# Sheet1_MCU.net
KiCad netlist of a schematic drawn in Altium Designer
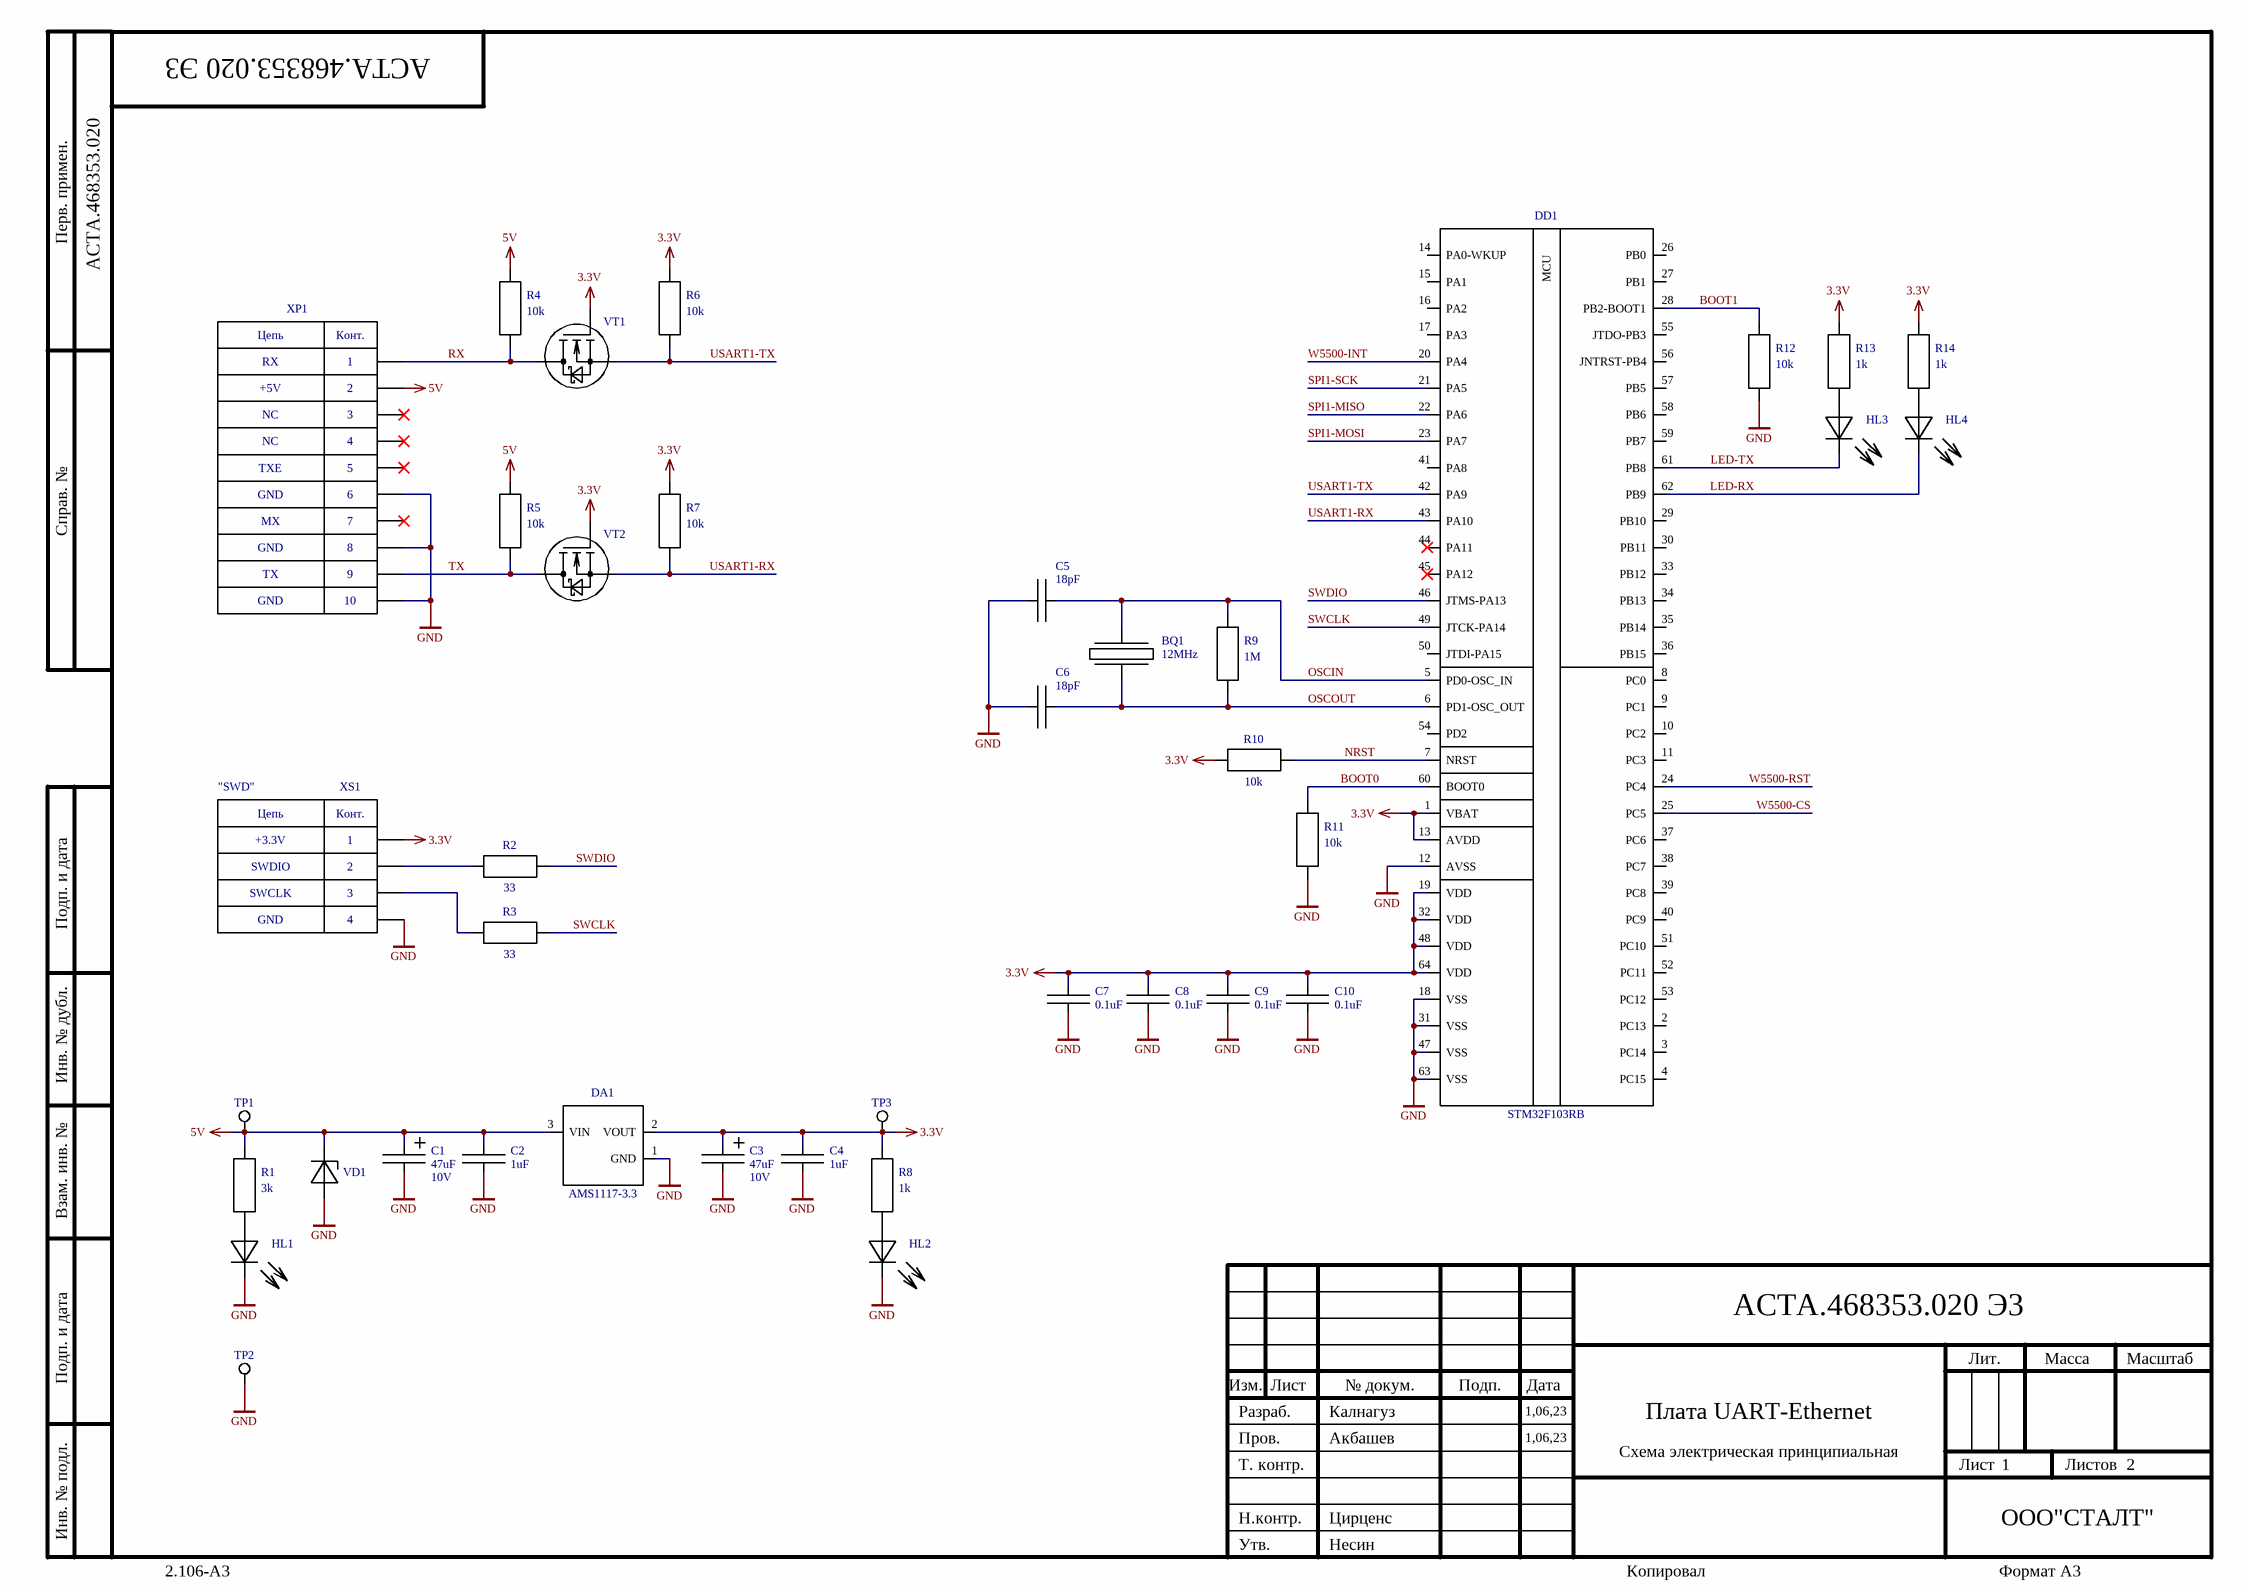
[diagram p0: Sheet1_MCU.SchDoc]

(export (version "E")
  (design (tool "Eeschema 10.0.6"))
  (components
    (comp (ref "BQ1")
      (value "12MHz")
      (footprint "HT-49S")
      (fields (field (name "Comment") "HT-49S_Rated"))
      (libsource (lib "Resonators") (part "HT-49S_Rated"))
    )
    (comp (ref "C1")
      (value "47uF")
      (footprint "CaseB_TantalumCap")
      (fields (field (name "VOLTAGE") "10V") (field (name "Comment") "CaseB_TantalumCap"))
      (libsource (lib "Tantalum_Capacitors") (part "CaseB_TantalumCap"))
    )
    (comp (ref "C2")
      (value "1uF")
      (footprint "CAP0805")
      (fields (field (name "Comment") "CAP0805_Rated"))
      (libsource (lib "Ceramic_Capacitors") (part "CAP0805_Rated"))
    )
    (comp (ref "C3")
      (value "47uF")
      (footprint "CaseB_TantalumCap")
      (fields (field (name "VOLTAGE") "10V") (field (name "Comment") "CaseB_TantalumCap"))
      (libsource (lib "Tantalum_Capacitors") (part "CaseB_TantalumCap"))
    )
    (comp (ref "C4")
      (value "1uF")
      (footprint "CAP0805")
      (fields (field (name "Comment") "CAP0805_Rated"))
      (libsource (lib "Ceramic_Capacitors") (part "CAP0805_Rated"))
    )
    (comp (ref "C5")
      (value "18pF")
      (footprint "CAP0805")
      (fields (field (name "Comment") "CAP0805_Rated"))
      (libsource (lib "Ceramic_Capacitors") (part "CAP0805_Rated"))
    )
    (comp (ref "C6")
      (value "18pF")
      (footprint "CAP0805")
      (fields (field (name "Comment") "CAP0805_Rated"))
      (libsource (lib "Ceramic_Capacitors") (part "CAP0805_Rated"))
    )
    (comp (ref "C7")
      (value "0.1uF")
      (footprint "CAP0805")
      (fields (field (name "Comment") "CAP0805_Rated"))
      (libsource (lib "Ceramic_Capacitors") (part "CAP0805_Rated"))
    )
    (comp (ref "C8")
      (value "0.1uF")
      (footprint "CAP0805")
      (fields (field (name "Comment") "CAP0805_Rated"))
      (libsource (lib "Ceramic_Capacitors") (part "CAP0805_Rated"))
    )
    (comp (ref "C9")
      (value "0.1uF")
      (footprint "CAP0805")
      (fields (field (name "Comment") "CAP0805_Rated"))
      (libsource (lib "Ceramic_Capacitors") (part "CAP0805_Rated"))
    )
    (comp (ref "C10")
      (value "0.1uF")
      (footprint "CAP0805")
      (fields (field (name "Comment") "CAP0805_Rated"))
      (libsource (lib "Ceramic_Capacitors") (part "CAP0805_Rated"))
    )
    (comp (ref "DA1")
      (value "AMS1117-3.3")
      (footprint "SOT-223")
      (description "Fixed Voltage 3.3V 1A Low Dropout Voltage Regulator")
      (libsource (lib "Power_Management_ICs") (part "AMS1117-3.3"))
    )
    (comp (ref "DD1")
      (value "STM32F103RB")
      (footprint "LQFP-64")
      (description "ARM Cortex-M3 MCU")
      (libsource (lib "MCU") (part "STM32F103RB"))
    )
    (comp (ref "HL1")
      (value "KPTD-3216MGC")
      (footprint "KPTD-3216 Green")
      (description "3.2x1.6mm SMD LED Mega Green")
      (libsource (lib "LEDs_SMD") (part "KPTD-3216MGC"))
    )
    (comp (ref "HL2")
      (value "KPTD-3216MGC")
      (footprint "KPTD-3216 Green")
      (description "3.2x1.6mm SMD LED Mega Green")
      (libsource (lib "LEDs_SMD") (part "KPTD-3216MGC"))
    )
    (comp (ref "HL3")
      (value "KPTD-3216MGC")
      (footprint "KPTD-3216 Green")
      (description "3.2x1.6mm SMD LED Mega Green")
      (libsource (lib "LEDs_SMD") (part "KPTD-3216MGC"))
    )
    (comp (ref "HL4")
      (value "KPTD-3216SYC")
      (footprint "KPTD-3216 Yellow")
      (description "3.2x1.6mm SMD LED Super Bright Yellow")
      (libsource (lib "LEDs_SMD") (part "KPTD-3216SYC"))
    )
    (comp (ref "R1")
      (value "3k")
      (footprint "RES0805")
      (fields (field (name "TOLERANCE") "5%") (field (name "Comment") "RES0805_Rated"))
      (libsource (lib "") (part "RES0805_Rated_1"))
    )
    (comp (ref "R2")
      (value "33")
      (footprint "RES0805")
      (fields (field (name "TOLERANCE") "5%") (field (name "Comment") "RES0805_Rated"))
      (libsource (lib "Resistors") (part "RES0805_Rated"))
    )
    (comp (ref "R3")
      (value "33")
      (footprint "RES0805")
      (fields (field (name "TOLERANCE") "5%") (field (name "Comment") "RES0805_Rated"))
      (libsource (lib "Resistors") (part "RES0805_Rated"))
    )
    (comp (ref "R4")
      (value "10k")
      (footprint "RES0805")
      (fields (field (name "TOLERANCE") "5%") (field (name "Comment") "RES0805_Rated"))
      (libsource (lib "") (part "RES0805_Rated_1"))
    )
    (comp (ref "R5")
      (value "10k")
      (footprint "RES0805")
      (fields (field (name "TOLERANCE") "5%") (field (name "Comment") "RES0805_Rated"))
      (libsource (lib "") (part "RES0805_Rated_1"))
    )
    (comp (ref "R6")
      (value "10k")
      (footprint "RES0805")
      (fields (field (name "TOLERANCE") "5%") (field (name "Comment") "RES0805_Rated"))
      (libsource (lib "") (part "RES0805_Rated_1"))
    )
    (comp (ref "R7")
      (value "10k")
      (footprint "RES0805")
      (fields (field (name "TOLERANCE") "5%") (field (name "Comment") "RES0805_Rated"))
      (libsource (lib "") (part "RES0805_Rated_1"))
    )
    (comp (ref "R8")
      (value "1k")
      (footprint "RES0805")
      (fields (field (name "TOLERANCE") "5%") (field (name "Comment") "RES0805_Rated"))
      (libsource (lib "") (part "RES0805_Rated_1"))
    )
    (comp (ref "R9")
      (value "1M")
      (footprint "RES0805")
      (fields (field (name "TOLERANCE") "5%") (field (name "Comment") "RES0805_Rated"))
      (libsource (lib "") (part "RES0805_Rated_1"))
    )
    (comp (ref "R10")
      (value "10k")
      (footprint "RES0805")
      (fields (field (name "TOLERANCE") "5%") (field (name "Comment") "RES0805_Rated"))
      (libsource (lib "Resistors") (part "RES0805_Rated"))
    )
    (comp (ref "R11")
      (value "10k")
      (footprint "RES0805")
      (fields (field (name "TOLERANCE") "5%") (field (name "Comment") "RES0805_Rated"))
      (libsource (lib "") (part "RES0805_Rated_1"))
    )
    (comp (ref "R12")
      (value "10k")
      (footprint "RES0805")
      (fields (field (name "TOLERANCE") "5%") (field (name "Comment") "RES0805_Rated"))
      (libsource (lib "") (part "RES0805_Rated_1"))
    )
    (comp (ref "R13")
      (value "1k")
      (footprint "RES0805")
      (fields (field (name "TOLERANCE") "5%") (field (name "Comment") "RES0805_Rated"))
      (libsource (lib "") (part "RES0805_Rated_1"))
    )
    (comp (ref "R14")
      (value "1k")
      (footprint "RES0805")
      (fields (field (name "TOLERANCE") "5%") (field (name "Comment") "RES0805_Rated"))
      (libsource (lib "") (part "RES0805_Rated_1"))
    )
    (comp (ref "TP1")
      (value "TestPad")
      (footprint "PAD-TH-OCT1x1-0.5")
      (description "TestPoint on PCB")
      (libsource (lib "Connectors") (part "TestPad"))
    )
    (comp (ref "TP2")
      (value "TestPad")
      (footprint "PAD-TH-OCT1x1-0.5")
      (description "TestPoint on PCB")
      (libsource (lib "Connectors") (part "TestPad"))
    )
    (comp (ref "TP3")
      (value "TestPad")
      (footprint "PAD-TH-OCT1x1-0.5")
      (description "TestPoint on PCB")
      (libsource (lib "Connectors") (part "TestPad"))
    )
    (comp (ref "VD1")
      (value "SMAJ5.0A")
      (footprint "SMA (DO-214AC)")
      (description "5Vr 400W 43.5A UniDirectional TVS")
      (libsource (lib "TVS_Diodes") (part "SMAJ5.0A"))
    )
    (comp (ref "VT1")
      (value "BSS138")
      (footprint "SOT-23")
      (description "Small Signal N-Channel MOSFET 50V 220mA")
      (libsource (lib "MOSFETs") (part "BSS138"))
    )
    (comp (ref "VT2")
      (value "BSS138")
      (footprint "SOT-23")
      (description "Small Signal N-Channel MOSFET 50V 220mA")
      (libsource (lib "MOSFETs") (part "BSS138"))
    )
    (comp (ref "XP1")
      (value "IDC-10MS")
      (footprint "IDC-10MS pad1.6x2.0")
      (description "Box Header Pitch 2.54mm")
      (fields
        (field (name "CIRCUIT7") "MX")
        (field (name "CIRCUIT8") "GND")
        (field (name "CIRCUIT9") "TX")
        (field (name "CIRCUIT10") "GND")
        (field (name "CIRCUIT6") "GND")
        (field (name "CIRCUIT4") "NC")
        (field (name "CIRCUIT5") "TXE")
        (field (name "CIRCUIT3") "NC")
        (field (name "CIRCUIT2") "+5V")
        (field (name "CIRCUIT1") "RX")
      )
      (libsource (lib "Connectors") (part "IDC-10MS"))
    )
    (comp (ref "XS1")
      (value "PBS-4")
      (footprint "PBS-4")
      (description "Female Header Pitch 2.54mm")
      (fields
        (field (name "CIRCUIT4") "GND")
        (field (name "CIRCUIT3") "SWCLK")
        (field (name "CIRCUIT1") "+3.3V")
        (field (name "CIRCUIT2") "SWDIO")
        (field (name "LABEL") "\"SWD\"")
      )
      (libsource (lib "Connectors") (part "PBS-4"))
    )
  )
  (nets
    (net (code "1") (name "/BOOT0") (class "Default")
      (node (ref "DD1") (pin "60") (pinfunction "BOOT0_60") (pintype "power_in"))
      (node (ref "R11") (pin "2") (pinfunction "2_2") (pintype "passive"))
    )
    (net (code "2") (name "/BOOT1") (class "Default")
      (node (ref "DD1") (pin "28") (pinfunction "PB2-BOOT1_28") (pintype "bidirectional"))
      (node (ref "R12") (pin "2") (pinfunction "2_2") (pintype "passive"))
    )
    (net (code "3") (name "/LED-RX") (class "Default")
      (node (ref "DD1") (pin "62") (pinfunction "PB9_62") (pintype "bidirectional"))
      (node (ref "HL4") (pin "K") (pinfunction "K_K") (pintype "passive"))
    )
    (net (code "4") (name "/LED-TX") (class "Default")
      (node (ref "DD1") (pin "61") (pinfunction "PB8_61") (pintype "bidirectional"))
      (node (ref "HL3") (pin "K") (pinfunction "K_K") (pintype "passive"))
    )
    (net (code "5") (name "/NRST") (class "Default")
      (node (ref "DD1") (pin "7") (pinfunction "NRST_7") (pintype "bidirectional"))
      (node (ref "R10") (pin "2") (pinfunction "2_2") (pintype "passive"))
    )
    (net (code "6") (name "/OSCIN") (class "Default")
      (node (ref "BQ1") (pin "1") (pinfunction "1_1") (pintype "passive"))
      (node (ref "C5") (pin "2") (pinfunction "2_2") (pintype "passive"))
      (node (ref "DD1") (pin "5") (pinfunction "PD0-OSC_IN_5") (pintype "bidirectional"))
      (node (ref "R9") (pin "2") (pinfunction "2_2") (pintype "passive"))
    )
    (net (code "7") (name "/OSCOUT") (class "Default")
      (node (ref "BQ1") (pin "2") (pinfunction "2_2") (pintype "passive"))
      (node (ref "C6") (pin "2") (pinfunction "2_2") (pintype "passive"))
      (node (ref "DD1") (pin "6") (pinfunction "PD1-OSC_OUT_6") (pintype "bidirectional"))
      (node (ref "R9") (pin "1") (pinfunction "1_1") (pintype "passive"))
    )
    (net (code "8") (name "/RX") (class "Default")
      (node (ref "R4") (pin "1") (pinfunction "1_1") (pintype "passive"))
      (node (ref "VT1") (pin "2") (pinfunction "D_2") (pintype "passive"))
      (node (ref "XP1") (pin "1") (pinfunction "1_1") (pintype "passive"))
    )
    (net (code "9") (name "/SPI1-MISO") (class "Default")
      (node (ref "DD1") (pin "22") (pinfunction "PA6_22") (pintype "bidirectional"))
    )
    (net (code "10") (name "/SPI1-MOSI") (class "Default")
      (node (ref "DD1") (pin "23") (pinfunction "PA7_23") (pintype "bidirectional"))
    )
    (net (code "11") (name "/SPI1-SCK") (class "Default")
      (node (ref "DD1") (pin "21") (pinfunction "PA5_21") (pintype "bidirectional"))
    )
    (net (code "12") (name "/SWCLK") (class "Default")
      (node (ref "DD1") (pin "49") (pinfunction "JTCK-PA14_49") (pintype "bidirectional"))
      (node (ref "R3") (pin "2") (pinfunction "2_2") (pintype "passive"))
    )
    (net (code "13") (name "/SWDIO") (class "Default")
      (node (ref "DD1") (pin "46") (pinfunction "JTMS-PA13_46") (pintype "bidirectional"))
      (node (ref "R2") (pin "2") (pinfunction "2_2") (pintype "passive"))
    )
    (net (code "14") (name "/TX") (class "Default")
      (node (ref "R5") (pin "1") (pinfunction "1_1") (pintype "passive"))
      (node (ref "VT2") (pin "2") (pinfunction "D_2") (pintype "passive"))
      (node (ref "XP1") (pin "9") (pinfunction "9_9") (pintype "passive"))
    )
    (net (code "15") (name "/USART1-RX") (class "Default")
      (node (ref "DD1") (pin "43") (pinfunction "PA10_43") (pintype "bidirectional"))
      (node (ref "R7") (pin "1") (pinfunction "1_1") (pintype "passive"))
      (node (ref "VT2") (pin "3") (pinfunction "S_3") (pintype "passive"))
    )
    (net (code "16") (name "/USART1-TX") (class "Default")
      (node (ref "DD1") (pin "42") (pinfunction "PA9_42") (pintype "bidirectional"))
      (node (ref "R6") (pin "1") (pinfunction "1_1") (pintype "passive"))
      (node (ref "VT1") (pin "3") (pinfunction "S_3") (pintype "passive"))
    )
    (net (code "17") (name "/W5500-CS") (class "Default")
      (node (ref "DD1") (pin "25") (pinfunction "PC5_25") (pintype "bidirectional"))
    )
    (net (code "18") (name "/W5500-INT") (class "Default")
      (node (ref "DD1") (pin "20") (pinfunction "PA4_20") (pintype "bidirectional"))
    )
    (net (code "19") (name "/W5500-RST") (class "Default")
      (node (ref "DD1") (pin "24") (pinfunction "PC4_24") (pintype "bidirectional"))
    )
    (net (code "20") (name "3.3V") (class "Default")
      (node (ref "C10") (pin "1") (pinfunction "1_1") (pintype "passive"))
      (node (ref "C3") (pin "1") (pinfunction "+_1") (pintype "passive"))
      (node (ref "C4") (pin "1") (pinfunction "1_1") (pintype "passive"))
      (node (ref "C7") (pin "1") (pinfunction "1_1") (pintype "passive"))
      (node (ref "C8") (pin "1") (pinfunction "1_1") (pintype "passive"))
      (node (ref "C9") (pin "1") (pinfunction "1_1") (pintype "passive"))
      (node (ref "DA1") (pin "2") (pinfunction "VOUT_2") (pintype "power_in"))
      (node (ref "DD1") (pin "1") (pinfunction "VBAT_1") (pintype "power_in"))
      (node (ref "DD1") (pin "13") (pinfunction "AVDD_13") (pintype "power_in"))
      (node (ref "DD1") (pin "19") (pinfunction "VDD_19") (pintype "power_in"))
      (node (ref "DD1") (pin "32") (pinfunction "VDD_32") (pintype "power_in"))
      (node (ref "DD1") (pin "48") (pinfunction "VDD_48") (pintype "power_in"))
      (node (ref "DD1") (pin "64") (pinfunction "VDD_64") (pintype "power_in"))
      (node (ref "R10") (pin "1") (pinfunction "1_1") (pintype "passive"))
      (node (ref "R13") (pin "2") (pinfunction "2_2") (pintype "passive"))
      (node (ref "R14") (pin "2") (pinfunction "2_2") (pintype "passive"))
      (node (ref "R6") (pin "2") (pinfunction "2_2") (pintype "passive"))
      (node (ref "R7") (pin "2") (pinfunction "2_2") (pintype "passive"))
      (node (ref "R8") (pin "2") (pinfunction "2_2") (pintype "passive"))
      (node (ref "TP3") (pin "1") (pinfunction "1_1") (pintype "passive"))
      (node (ref "VT1") (pin "1") (pinfunction "G_1") (pintype "passive"))
      (node (ref "VT2") (pin "1") (pinfunction "G_1") (pintype "passive"))
      (node (ref "XS1") (pin "1") (pinfunction "1_1") (pintype "passive"))
    )
    (net (code "21") (name "5V") (class "Default")
      (node (ref "C1") (pin "1") (pinfunction "+_1") (pintype "passive"))
      (node (ref "C2") (pin "1") (pinfunction "1_1") (pintype "passive"))
      (node (ref "DA1") (pin "3") (pinfunction "VIN_3") (pintype "power_in"))
      (node (ref "R1") (pin "2") (pinfunction "2_2") (pintype "passive"))
      (node (ref "R4") (pin "2") (pinfunction "2_2") (pintype "passive"))
      (node (ref "R5") (pin "2") (pinfunction "2_2") (pintype "passive"))
      (node (ref "TP1") (pin "1") (pinfunction "1_1") (pintype "passive"))
      (node (ref "VD1") (pin "K") (pinfunction "K_K") (pintype "passive"))
      (node (ref "XP1") (pin "2") (pinfunction "2_2") (pintype "passive"))
    )
    (net (code "22") (name "GND") (class "Default")
      (node (ref "C1") (pin "2") (pinfunction "-_2") (pintype "passive"))
      (node (ref "C10") (pin "2") (pinfunction "2_2") (pintype "passive"))
      (node (ref "C2") (pin "2") (pinfunction "2_2") (pintype "passive"))
      (node (ref "C3") (pin "2") (pinfunction "-_2") (pintype "passive"))
      (node (ref "C4") (pin "2") (pinfunction "2_2") (pintype "passive"))
      (node (ref "C5") (pin "1") (pinfunction "1_1") (pintype "passive"))
      (node (ref "C6") (pin "1") (pinfunction "1_1") (pintype "passive"))
      (node (ref "C7") (pin "2") (pinfunction "2_2") (pintype "passive"))
      (node (ref "C8") (pin "2") (pinfunction "2_2") (pintype "passive"))
      (node (ref "C9") (pin "2") (pinfunction "2_2") (pintype "passive"))
      (node (ref "DA1") (pin "1") (pinfunction "GND_1") (pintype "power_in"))
      (node (ref "DD1") (pin "12") (pinfunction "AVSS_12") (pintype "power_in"))
      (node (ref "DD1") (pin "18") (pinfunction "VSS_18") (pintype "power_in"))
      (node (ref "DD1") (pin "31") (pinfunction "VSS_31") (pintype "power_in"))
      (node (ref "DD1") (pin "47") (pinfunction "VSS_47") (pintype "power_in"))
      (node (ref "DD1") (pin "63") (pinfunction "VSS_63") (pintype "power_in"))
      (node (ref "HL1") (pin "K") (pinfunction "K_K") (pintype "passive"))
      (node (ref "HL2") (pin "K") (pinfunction "K_K") (pintype "passive"))
      (node (ref "R11") (pin "1") (pinfunction "1_1") (pintype "passive"))
      (node (ref "R12") (pin "1") (pinfunction "1_1") (pintype "passive"))
      (node (ref "TP2") (pin "1") (pinfunction "1_1") (pintype "passive"))
      (node (ref "VD1") (pin "A") (pinfunction "A_A") (pintype "passive"))
      (node (ref "XP1") (pin "10") (pinfunction "10_10") (pintype "passive"))
      (node (ref "XP1") (pin "6") (pinfunction "6_6") (pintype "passive"))
      (node (ref "XP1") (pin "8") (pinfunction "8_8") (pintype "passive"))
      (node (ref "XS1") (pin "4") (pinfunction "4_4") (pintype "passive"))
    )
    (net (code "23") (name "Net-(HL1-PadA)") (class "Default")
      (node (ref "HL1") (pin "A") (pinfunction "A_A") (pintype "passive"))
      (node (ref "R1") (pin "1") (pinfunction "1_1") (pintype "passive"))
    )
    (net (code "24") (name "Net-(HL2-PadA)") (class "Default")
      (node (ref "HL2") (pin "A") (pinfunction "A_A") (pintype "passive"))
      (node (ref "R8") (pin "1") (pinfunction "1_1") (pintype "passive"))
    )
    (net (code "25") (name "Net-(HL3-PadA)") (class "Default")
      (node (ref "HL3") (pin "A") (pinfunction "A_A") (pintype "passive"))
      (node (ref "R13") (pin "1") (pinfunction "1_1") (pintype "passive"))
    )
    (net (code "26") (name "Net-(HL4-PadA)") (class "Default")
      (node (ref "HL4") (pin "A") (pinfunction "A_A") (pintype "passive"))
      (node (ref "R14") (pin "1") (pinfunction "1_1") (pintype "passive"))
    )
    (net (code "27") (name "Net-(R2-Pad1)") (class "Default")
      (node (ref "R2") (pin "1") (pinfunction "1_1") (pintype "passive"))
      (node (ref "XS1") (pin "2") (pinfunction "2_2") (pintype "passive"))
    )
    (net (code "28") (name "Net-(R3-Pad1)") (class "Default")
      (node (ref "R3") (pin "1") (pinfunction "1_1") (pintype "passive"))
      (node (ref "XS1") (pin "3") (pinfunction "3_3") (pintype "passive"))
    )
    (net (code "29") (name "unconnected-(DD1-JNTRST-PB4-Pad56)") (class "Default")
      (node (ref "DD1") (pin "56") (pinfunction "JNTRST-PB4_56") (pintype "bidirectional"))
    )
    (net (code "30") (name "unconnected-(DD1-JTDI-PA15-Pad50)") (class "Default")
      (node (ref "DD1") (pin "50") (pinfunction "JTDI-PA15_50") (pintype "bidirectional"))
    )
    (net (code "31") (name "unconnected-(DD1-JTDO-PB3-Pad55)") (class "Default")
      (node (ref "DD1") (pin "55") (pinfunction "JTDO-PB3_55") (pintype "bidirectional"))
    )
    (net (code "32") (name "unconnected-(DD1-PA0-WKUP-Pad14)") (class "Default")
      (node (ref "DD1") (pin "14") (pinfunction "PA0-WKUP_14") (pintype "bidirectional"))
    )
    (net (code "33") (name "unconnected-(DD1-PA1-Pad15)") (class "Default")
      (node (ref "DD1") (pin "15") (pinfunction "PA1_15") (pintype "bidirectional"))
    )
    (net (code "34") (name "unconnected-(DD1-PA2-Pad16)") (class "Default")
      (node (ref "DD1") (pin "16") (pinfunction "PA2_16") (pintype "bidirectional"))
    )
    (net (code "35") (name "unconnected-(DD1-PA3-Pad17)") (class "Default")
      (node (ref "DD1") (pin "17") (pinfunction "PA3_17") (pintype "bidirectional"))
    )
    (net (code "36") (name "unconnected-(DD1-PA8-Pad41)") (class "Default")
      (node (ref "DD1") (pin "41") (pinfunction "PA8_41") (pintype "bidirectional"))
    )
    (net (code "37") (name "unconnected-(DD1-PA11-Pad44)") (class "Default")
      (node (ref "DD1") (pin "44") (pinfunction "PA11_44") (pintype "bidirectional+no_connect"))
    )
    (net (code "38") (name "unconnected-(DD1-PA12-Pad45)") (class "Default")
      (node (ref "DD1") (pin "45") (pinfunction "PA12_45") (pintype "bidirectional+no_connect"))
    )
    (net (code "39") (name "unconnected-(DD1-PB0-Pad26)") (class "Default")
      (node (ref "DD1") (pin "26") (pinfunction "PB0_26") (pintype "bidirectional"))
    )
    (net (code "40") (name "unconnected-(DD1-PB1-Pad27)") (class "Default")
      (node (ref "DD1") (pin "27") (pinfunction "PB1_27") (pintype "bidirectional"))
    )
    (net (code "41") (name "unconnected-(DD1-PB5-Pad57)") (class "Default")
      (node (ref "DD1") (pin "57") (pinfunction "PB5_57") (pintype "bidirectional"))
    )
    (net (code "42") (name "unconnected-(DD1-PB6-Pad58)") (class "Default")
      (node (ref "DD1") (pin "58") (pinfunction "PB6_58") (pintype "bidirectional"))
    )
    (net (code "43") (name "unconnected-(DD1-PB7-Pad59)") (class "Default")
      (node (ref "DD1") (pin "59") (pinfunction "PB7_59") (pintype "bidirectional"))
    )
    (net (code "44") (name "unconnected-(DD1-PB10-Pad29)") (class "Default")
      (node (ref "DD1") (pin "29") (pinfunction "PB10_29") (pintype "bidirectional"))
    )
    (net (code "45") (name "unconnected-(DD1-PB11-Pad30)") (class "Default")
      (node (ref "DD1") (pin "30") (pinfunction "PB11_30") (pintype "bidirectional"))
    )
    (net (code "46") (name "unconnected-(DD1-PB12-Pad33)") (class "Default")
      (node (ref "DD1") (pin "33") (pinfunction "PB12_33") (pintype "bidirectional"))
    )
    (net (code "47") (name "unconnected-(DD1-PB13-Pad34)") (class "Default")
      (node (ref "DD1") (pin "34") (pinfunction "PB13_34") (pintype "bidirectional"))
    )
    (net (code "48") (name "unconnected-(DD1-PB14-Pad35)") (class "Default")
      (node (ref "DD1") (pin "35") (pinfunction "PB14_35") (pintype "bidirectional"))
    )
    (net (code "49") (name "unconnected-(DD1-PB15-Pad36)") (class "Default")
      (node (ref "DD1") (pin "36") (pinfunction "PB15_36") (pintype "bidirectional"))
    )
    (net (code "50") (name "unconnected-(DD1-PC0-Pad8)") (class "Default")
      (node (ref "DD1") (pin "8") (pinfunction "PC0_8") (pintype "bidirectional"))
    )
    (net (code "51") (name "unconnected-(DD1-PC1-Pad9)") (class "Default")
      (node (ref "DD1") (pin "9") (pinfunction "PC1_9") (pintype "bidirectional"))
    )
    (net (code "52") (name "unconnected-(DD1-PC2-Pad10)") (class "Default")
      (node (ref "DD1") (pin "10") (pinfunction "PC2_10") (pintype "bidirectional"))
    )
    (net (code "53") (name "unconnected-(DD1-PC3-Pad11)") (class "Default")
      (node (ref "DD1") (pin "11") (pinfunction "PC3_11") (pintype "bidirectional"))
    )
    (net (code "54") (name "unconnected-(DD1-PC6-Pad37)") (class "Default")
      (node (ref "DD1") (pin "37") (pinfunction "PC6_37") (pintype "bidirectional"))
    )
    (net (code "55") (name "unconnected-(DD1-PC7-Pad38)") (class "Default")
      (node (ref "DD1") (pin "38") (pinfunction "PC7_38") (pintype "bidirectional"))
    )
    (net (code "56") (name "unconnected-(DD1-PC8-Pad39)") (class "Default")
      (node (ref "DD1") (pin "39") (pinfunction "PC8_39") (pintype "bidirectional"))
    )
    (net (code "57") (name "unconnected-(DD1-PC9-Pad40)") (class "Default")
      (node (ref "DD1") (pin "40") (pinfunction "PC9_40") (pintype "bidirectional"))
    )
    (net (code "58") (name "unconnected-(DD1-PC10-Pad51)") (class "Default")
      (node (ref "DD1") (pin "51") (pinfunction "PC10_51") (pintype "bidirectional"))
    )
    (net (code "59") (name "unconnected-(DD1-PC11-Pad52)") (class "Default")
      (node (ref "DD1") (pin "52") (pinfunction "PC11_52") (pintype "bidirectional"))
    )
    (net (code "60") (name "unconnected-(DD1-PC12-Pad53)") (class "Default")
      (node (ref "DD1") (pin "53") (pinfunction "PC12_53") (pintype "bidirectional"))
    )
    (net (code "61") (name "unconnected-(DD1-PC13-Pad2)") (class "Default")
      (node (ref "DD1") (pin "2") (pinfunction "PC13_2") (pintype "bidirectional"))
    )
    (net (code "62") (name "unconnected-(DD1-PC14-Pad3)") (class "Default")
      (node (ref "DD1") (pin "3") (pinfunction "PC14_3") (pintype "bidirectional"))
    )
    (net (code "63") (name "unconnected-(DD1-PC15-Pad4)") (class "Default")
      (node (ref "DD1") (pin "4") (pinfunction "PC15_4") (pintype "bidirectional"))
    )
    (net (code "64") (name "unconnected-(DD1-PD2-Pad54)") (class "Default")
      (node (ref "DD1") (pin "54") (pinfunction "PD2_54") (pintype "bidirectional"))
    )
    (net (code "65") (name "unconnected-(XP1-Pad3)") (class "Default")
      (node (ref "XP1") (pin "3") (pinfunction "3_3") (pintype "passive+no_connect"))
    )
    (net (code "66") (name "unconnected-(XP1-Pad4)") (class "Default")
      (node (ref "XP1") (pin "4") (pinfunction "4_4") (pintype "passive+no_connect"))
    )
    (net (code "67") (name "unconnected-(XP1-Pad5)") (class "Default")
      (node (ref "XP1") (pin "5") (pinfunction "5_5") (pintype "passive+no_connect"))
    )
    (net (code "68") (name "unconnected-(XP1-Pad7)") (class "Default")
      (node (ref "XP1") (pin "7") (pinfunction "7_7") (pintype "passive+no_connect"))
    )
  )
)
